# Motor-Y.net
KiCad netlist of a schematic drawn in Altium Designer
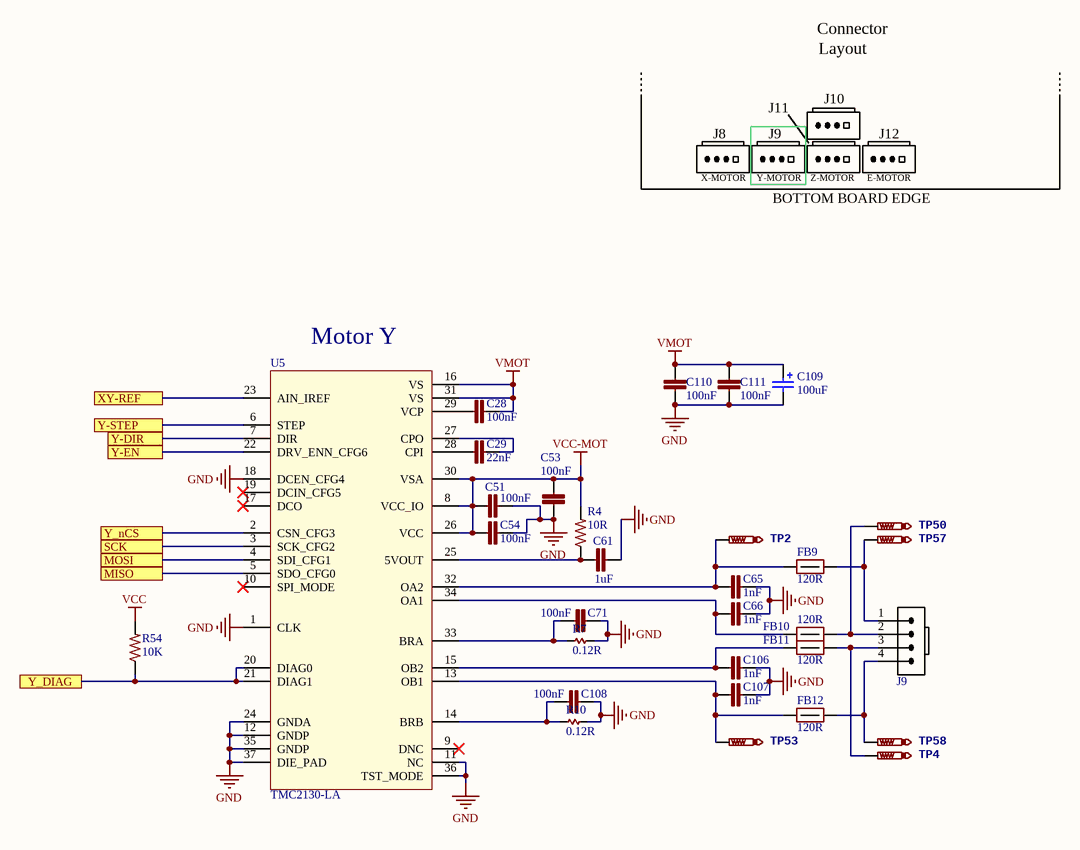
[diagram p0: Motor-Y.SchDoc]

(export (version "E")
  (design (tool "Eeschema 10.0.6"))
  (components
    (comp (ref "C28")
      (value "100nF")
      (footprint "C0603")
      (description "CAP CER 0603 100nF 50V 10% X7R")
      (fields (field (name "MANUFACTURER") "Kemet") (field (name "TOLERANCE") "+/- 10%"))
      (libsource (lib "") (part "C0603C104K5RACTU_1"))
    )
    (comp (ref "C29")
      (value "22nF")
      (footprint "C0402")
      (description "CAP CER 0402 22nF ±10% 50V X7R")
      (fields (field (name "MANUFACTURER") "YAGEO") (field (name "TOLERANCE") "+/- 10%"))
      (libsource (lib "3Delight") (part "GCM155R71H223KA55D"))
    )
    (comp (ref "C51")
      (value "100nF")
      (footprint "C0402")
      (description "CAP CER 0402 100nF 16V 10% X7R")
      (fields (field (name "MANUFACTURER") "Murata") (field (name "TOLERANCE") "+/- 10%"))
      (libsource (lib "3Delight") (part "GRM155R71C104KA88D"))
    )
    (comp (ref "C53")
      (value "100nF")
      (footprint "C0402")
      (description "CAP CER 0402 100nF 16V 10% X7R")
      (fields (field (name "MANUFACTURER") "Murata") (field (name "TOLERANCE") "+/- 10%"))
      (libsource (lib "") (part "GRM155R71C104KA88D_1"))
    )
    (comp (ref "C54")
      (value "100nF")
      (footprint "C0402")
      (description "CAP CER 0402 100nF 16V 10% X7R")
      (fields (field (name "MANUFACTURER") "Murata") (field (name "TOLERANCE") "+/- 10%"))
      (libsource (lib "3Delight") (part "GRM155R71C104KA88D"))
    )
    (comp (ref "C61")
      (value "1uF")
      (footprint "C0402")
      (description "CAP CER 0402 1uF 6.3V 10% X5R")
      (fields (field (name "MANUFACTURER") "Murata") (field (name "TOLERANCE") "+/- 10%"))
      (libsource (lib "3Delight") (part "GRM155R60J105KE19D"))
    )
    (comp (ref "C65")
      (value "1nF")
      (footprint "C0603")
      (description "CAP CER 0603  1nF 50v 10% X7R")
      (fields (field (name "MANUFACTURER") "Kemet") (field (name "TOLERANCE") "+/- 10%"))
      (libsource (lib "3Delight") (part "C0603C102K5RACTU"))
    )
    (comp (ref "C66")
      (value "1nF")
      (footprint "C0603")
      (description "CAP CER 0603  1nF 50v 10% X7R")
      (fields (field (name "MANUFACTURER") "Kemet") (field (name "TOLERANCE") "+/- 10%"))
      (libsource (lib "3Delight") (part "C0603C102K5RACTU"))
    )
    (comp (ref "C71")
      (value "100nF")
      (footprint "C0603")
      (description "CAP CER 0603 100nF 50V 10% X7R")
      (fields (field (name "MANUFACTURER") "Kemet") (field (name "TOLERANCE") "+/- 10%"))
      (libsource (lib "3Delight") (part "C0603C104K5RACTU"))
    )
    (comp (ref "C106")
      (value "1nF")
      (footprint "C0603")
      (description "CAP CER 0603  1nF 50v 10% X7R")
      (fields (field (name "MANUFACTURER") "Kemet") (field (name "TOLERANCE") "+/- 10%"))
      (libsource (lib "3Delight") (part "C0603C102K5RACTU"))
    )
    (comp (ref "C107")
      (value "1nF")
      (footprint "C0603")
      (description "CAP CER 0603  1nF 50v 10% X7R")
      (fields (field (name "MANUFACTURER") "Kemet") (field (name "TOLERANCE") "+/- 10%"))
      (libsource (lib "3Delight") (part "C0603C102K5RACTU"))
    )
    (comp (ref "C108")
      (value "100nF")
      (footprint "C0603")
      (description "CAP CER 0603 100nF 50V 10% X7R")
      (fields (field (name "MANUFACTURER") "Kemet") (field (name "TOLERANCE") "+/- 10%"))
      (libsource (lib "3Delight") (part "C0603C104K5RACTU"))
    )
    (comp (ref "C109")
      (value "100uF")
      (footprint "CAP-ELEC-063063077")
      (description "CAP ALUM 100UF 35V 20% SMD")
      (fields (field (name "MANUFACTURER") "Nichicon") (field (name "TOLERANCE") "+/- 20%"))
      (libsource (lib "3Delight") (part "UWT1V101MCL1GS"))
    )
    (comp (ref "C110")
      (value "100nF")
      (footprint "C0603")
      (description "CAP CER 0603 100nF 50V 10% X7R")
      (fields (field (name "MANUFACTURER") "Kemet") (field (name "TOLERANCE") "+/- 10%"))
      (libsource (lib "") (part "C0603C104K5RACTU_2"))
    )
    (comp (ref "C111")
      (value "100nF")
      (footprint "C0603")
      (description "CAP CER 0603 100nF 50V 10% X7R")
      (fields (field (name "MANUFACTURER") "Kemet") (field (name "TOLERANCE") "+/- 10%"))
      (libsource (lib "") (part "C0603C104K5RACTU_2"))
    )
    (comp (ref "FB9")
      (value "120R")
      (footprint "FB0603")
      (description "FERRITE BEAD 120 OHM 0603 1LN")
      (fields (field (name "MANUFACTURER") "Samsung") (field (name "PART") "FERRITE 120R 3A 0603"))
      (libsource (lib "Inductors") (part "FERRITE 120R 3A 0603"))
    )
    (comp (ref "FB10")
      (value "120R")
      (footprint "FB0603")
      (description "FERRITE BEAD 120 OHM 0603 1LN")
      (fields (field (name "MANUFACTURER") "Samsung") (field (name "PART") "FERRITE 120R 3A 0603"))
      (libsource (lib "Inductors") (part "FERRITE 120R 3A 0603"))
    )
    (comp (ref "FB11")
      (value "120R")
      (footprint "FB0603")
      (description "FERRITE BEAD 120 OHM 0603 1LN")
      (fields (field (name "MANUFACTURER") "Samsung") (field (name "PART") "FERRITE 120R 3A 0603"))
      (libsource (lib "Inductors") (part "FERRITE 120R 3A 0603"))
    )
    (comp (ref "FB12")
      (value "120R")
      (footprint "FB0603")
      (description "FERRITE BEAD 120 OHM 0603 1LN")
      (fields (field (name "MANUFACTURER") "Samsung") (field (name "PART") "FERRITE 120R 3A 0603"))
      (libsource (lib "Inductors") (part "FERRITE 120R 3A 0603"))
    )
    (comp (ref "J9")
      (value "Molex 0705430003")
      (footprint "4POL254 PIN-IN-PASTE")
      (description "Molex 4 Pin Clip Connector - Pin In Paste footprint")
      (libsource (lib "Connectors") (part "Molex 0705430003 PIP"))
    )
    (comp (ref "R4")
      (value "10R")
      (footprint "R0402")
      (description "RES SMD 10 OHM 1% 1/16W 0402")
      (fields (field (name "MANUFACTURER") "Yageo") (field (name "TOLERANCE") "+/- 1%"))
      (libsource (lib "3Delight") (part "RC0402FR-0710RL"))
    )
    (comp (ref "R7")
      (value "0.12R")
      (footprint "R1206")
      (description "RES 0.12 OHM 1% 1/2W 1206")
      (fields (field (name "TOLERANCE") "+/- 1%"))
      (libsource (lib "Resistors") (part "0.12R 1% 1206"))
    )
    (comp (ref "R10")
      (value "0.12R")
      (footprint "R1206")
      (description "RES 0.12 OHM 1% 1/2W 1206")
      (fields (field (name "TOLERANCE") "+/- 1%"))
      (libsource (lib "Resistors") (part "0.12R 1% 1206"))
    )
    (comp (ref "R54")
      (value "10K")
      (footprint "R0402")
      (description "RES SMD 10K OHM 1% 1/16W 0402")
      (fields (field (name "MANUFACTURER") "Yageo") (field (name "PART") "10k 1% 0402"))
      (libsource (lib "3Delight") (part "RC0402FR-0710KP"))
    )
    (comp (ref "TP2")
      (value "TestPoint")
      (footprint "TP1-27")
      (description "Test Point")
      (libsource (lib "3Delight") (part "TestPoint"))
    )
    (comp (ref "TP4")
      (value "TestPoint")
      (footprint "TP1-27")
      (description "Test Point")
      (libsource (lib "3Delight") (part "TestPoint"))
    )
    (comp (ref "TP50")
      (value "TestPoint")
      (footprint "TP1-27")
      (description "Test Point")
      (libsource (lib "3Delight") (part "TestPoint"))
    )
    (comp (ref "TP53")
      (value "TestPoint")
      (footprint "TP1-27")
      (description "Test Point")
      (libsource (lib "3Delight") (part "TestPoint"))
    )
    (comp (ref "TP57")
      (value "TestPoint")
      (footprint "TP1-27")
      (description "Test Point")
      (libsource (lib "3Delight") (part "TestPoint"))
    )
    (comp (ref "TP58")
      (value "TestPoint")
      (footprint "TP1-27")
      (description "Test Point")
      (libsource (lib "3Delight") (part "TestPoint"))
    )
    (comp (ref "U5")
      (value "TMC2130-LA")
      (footprint "QFN36-50P500X600X900_HS-37N")
      (description "IC STEPPER MOTOR DVR SPI 36QFN")
      (fields (field (name "MANUFACTURER") "Trinamic") (field (name "PART") "TMC2130"))
      (libsource (lib "3Delight") (part "TMC2130-LA-T"))
    )
  )
  (nets
    (net (code "1") (name "/MISO") (class "Default")
      (node (ref "U5") (pin "5") (pinfunction "SDO_CFG0_5") (pintype "passive"))
    )
    (net (code "2") (name "/MOSI") (class "Default")
      (node (ref "U5") (pin "4") (pinfunction "SDI_CFG1_4") (pintype "passive"))
    )
    (net (code "3") (name "/SCK") (class "Default")
      (node (ref "U5") (pin "3") (pinfunction "SCK_CFG2_3") (pintype "passive"))
    )
    (net (code "4") (name "/XY-REF") (class "Default")
      (node (ref "U5") (pin "23") (pinfunction "AIN_IREF_23") (pintype "passive"))
    )
    (net (code "5") (name "/Y-DIR") (class "Default")
      (node (ref "U5") (pin "7") (pinfunction "DIR_7") (pintype "passive"))
    )
    (net (code "6") (name "/Y-EN") (class "Default")
      (node (ref "U5") (pin "22") (pinfunction "DRV_ENN_CFG6_22") (pintype "passive"))
    )
    (net (code "7") (name "/Y-STEP") (class "Default")
      (node (ref "U5") (pin "6") (pinfunction "STEP_6") (pintype "passive"))
    )
    (net (code "8") (name "/Y_DIAG") (class "Default")
      (node (ref "R54") (pin "1") (pinfunction "1_1") (pintype "passive"))
      (node (ref "U5") (pin "20") (pinfunction "DIAG0_20") (pintype "passive"))
      (node (ref "U5") (pin "21") (pinfunction "DIAG1_21") (pintype "passive"))
    )
    (net (code "9") (name "/Y_nCS") (class "Default")
      (node (ref "U5") (pin "2") (pinfunction "CSN_CFG3_2") (pintype "passive"))
    )
    (net (code "10") (name "GND") (class "Default")
      (node (ref "C106") (pin "2") (pinfunction "2_2") (pintype "passive"))
      (node (ref "C107") (pin "2") (pinfunction "2_2") (pintype "passive"))
      (node (ref "C108") (pin "1") (pinfunction "1_1") (pintype "passive"))
      (node (ref "C109") (pin "2") (pinfunction "2_2") (pintype "passive"))
      (node (ref "C110") (pin "1") (pinfunction "1_1") (pintype "passive"))
      (node (ref "C111") (pin "1") (pinfunction "1_1") (pintype "passive"))
      (node (ref "C51") (pin "1") (pinfunction "1_1") (pintype "passive"))
      (node (ref "C53") (pin "1") (pinfunction "1_1") (pintype "passive"))
      (node (ref "C54") (pin "1") (pinfunction "1_1") (pintype "passive"))
      (node (ref "C61") (pin "2") (pinfunction "2_2") (pintype "passive"))
      (node (ref "C65") (pin "2") (pinfunction "2_2") (pintype "passive"))
      (node (ref "C66") (pin "2") (pinfunction "2_2") (pintype "passive"))
      (node (ref "C71") (pin "1") (pinfunction "1_1") (pintype "passive"))
      (node (ref "R10") (pin "2") (pinfunction "2_2") (pintype "passive"))
      (node (ref "R7") (pin "2") (pinfunction "2_2") (pintype "passive"))
      (node (ref "U5") (pin "1") (pinfunction "CLK_1") (pintype "passive"))
      (node (ref "U5") (pin "11") (pinfunction "NC_11") (pintype "passive"))
      (node (ref "U5") (pin "12") (pinfunction "GNDP_12") (pintype "passive"))
      (node (ref "U5") (pin "18") (pinfunction "DCEN_CFG4_18") (pintype "passive"))
      (node (ref "U5") (pin "24") (pinfunction "GNDA_24") (pintype "passive"))
      (node (ref "U5") (pin "35") (pinfunction "GNDP_35") (pintype "passive"))
      (node (ref "U5") (pin "36") (pinfunction "TST_MODE_36") (pintype "passive"))
      (node (ref "U5") (pin "37") (pinfunction "DIE_PAD_37") (pintype "passive"))
    )
    (net (code "11") (name "Net-(FB9-Pad2)") (class "Default")
      (node (ref "FB9") (pin "2") (pinfunction "2_2") (pintype "passive"))
      (node (ref "J9") (pin "1") (pinfunction "1_1") (pintype "passive"))
      (node (ref "TP57") (pin "TP") (pinfunction "TP_TP") (pintype "passive"))
    )
    (net (code "12") (name "Net-(FB10-Pad2)") (class "Default")
      (node (ref "FB10") (pin "2") (pinfunction "2_2") (pintype "passive"))
      (node (ref "J9") (pin "2") (pinfunction "2_2") (pintype "passive"))
      (node (ref "TP50") (pin "TP") (pinfunction "TP_TP") (pintype "passive"))
    )
    (net (code "13") (name "Net-(FB11-Pad2)") (class "Default")
      (node (ref "FB11") (pin "2") (pinfunction "2_2") (pintype "passive"))
      (node (ref "J9") (pin "3") (pinfunction "3_3") (pintype "passive"))
      (node (ref "TP4") (pin "TP") (pinfunction "TP_TP") (pintype "passive"))
    )
    (net (code "14") (name "Net-(FB12-Pad2)") (class "Default")
      (node (ref "FB12") (pin "2") (pinfunction "2_2") (pintype "passive"))
      (node (ref "J9") (pin "4") (pinfunction "4_4") (pintype "passive"))
      (node (ref "TP58") (pin "TP") (pinfunction "TP_TP") (pintype "passive"))
    )
    (net (code "15") (name "Net-(U5-5VOUT)") (class "Default")
      (node (ref "C61") (pin "1") (pinfunction "1_1") (pintype "passive"))
      (node (ref "R4") (pin "1") (pinfunction "1_1") (pintype "passive"))
      (node (ref "U5") (pin "25") (pinfunction "5VOUT_25") (pintype "passive"))
    )
    (net (code "16") (name "Net-(U5-BRA)") (class "Default")
      (node (ref "C71") (pin "2") (pinfunction "2_2") (pintype "passive"))
      (node (ref "R7") (pin "1") (pinfunction "1_1") (pintype "passive"))
      (node (ref "U5") (pin "33") (pinfunction "BRA_33") (pintype "passive"))
    )
    (net (code "17") (name "Net-(U5-BRB)") (class "Default")
      (node (ref "C108") (pin "2") (pinfunction "2_2") (pintype "passive"))
      (node (ref "R10") (pin "1") (pinfunction "1_1") (pintype "passive"))
      (node (ref "U5") (pin "14") (pinfunction "BRB_14") (pintype "passive"))
    )
    (net (code "18") (name "Net-(U5-CPI)") (class "Default")
      (node (ref "C29") (pin "1") (pinfunction "1_1") (pintype "passive"))
      (node (ref "U5") (pin "28") (pinfunction "CPI_28") (pintype "passive"))
    )
    (net (code "19") (name "Net-(U5-CPO)") (class "Default")
      (node (ref "C29") (pin "2") (pinfunction "2_2") (pintype "passive"))
      (node (ref "U5") (pin "27") (pinfunction "CPO_27") (pintype "passive"))
    )
    (net (code "20") (name "Net-(U5-OA1)") (class "Default")
      (node (ref "C66") (pin "1") (pinfunction "1_1") (pintype "passive"))
      (node (ref "FB10") (pin "1") (pinfunction "1_1") (pintype "passive"))
      (node (ref "U5") (pin "34") (pinfunction "OA1_34") (pintype "passive"))
    )
    (net (code "21") (name "Net-(U5-OA2)") (class "Default")
      (node (ref "C65") (pin "1") (pinfunction "1_1") (pintype "passive"))
      (node (ref "FB9") (pin "1") (pinfunction "1_1") (pintype "passive"))
      (node (ref "TP2") (pin "TP") (pinfunction "TP_TP") (pintype "passive"))
      (node (ref "U5") (pin "32") (pinfunction "OA2_32") (pintype "passive"))
    )
    (net (code "22") (name "Net-(U5-OB1)") (class "Default")
      (node (ref "C107") (pin "1") (pinfunction "1_1") (pintype "passive"))
      (node (ref "FB12") (pin "1") (pinfunction "1_1") (pintype "passive"))
      (node (ref "TP53") (pin "TP") (pinfunction "TP_TP") (pintype "passive"))
      (node (ref "U5") (pin "13") (pinfunction "OB1_13") (pintype "passive"))
    )
    (net (code "23") (name "Net-(U5-OB2)") (class "Default")
      (node (ref "C106") (pin "1") (pinfunction "1_1") (pintype "passive"))
      (node (ref "FB11") (pin "1") (pinfunction "1_1") (pintype "passive"))
      (node (ref "U5") (pin "15") (pinfunction "OB2_15") (pintype "passive"))
    )
    (net (code "24") (name "Net-(U5-VCP)") (class "Default")
      (node (ref "C28") (pin "1") (pinfunction "1_1") (pintype "passive"))
      (node (ref "U5") (pin "29") (pinfunction "VCP_29") (pintype "passive"))
    )
    (net (code "25") (name "VCC") (class "Default")
      (node (ref "R54") (pin "2") (pinfunction "2_2") (pintype "passive"))
    )
    (net (code "26") (name "VCC-MOT") (class "Default")
      (node (ref "C51") (pin "2") (pinfunction "2_2") (pintype "passive"))
      (node (ref "C53") (pin "2") (pinfunction "2_2") (pintype "passive"))
      (node (ref "C54") (pin "2") (pinfunction "2_2") (pintype "passive"))
      (node (ref "R4") (pin "2") (pinfunction "2_2") (pintype "passive"))
      (node (ref "U5") (pin "26") (pinfunction "VCC_26") (pintype "passive"))
      (node (ref "U5") (pin "30") (pinfunction "VSA_30") (pintype "passive"))
      (node (ref "U5") (pin "8") (pinfunction "VCC_IO_8") (pintype "passive"))
    )
    (net (code "27") (name "VMOT") (class "Default")
      (node (ref "C109") (pin "1") (pinfunction "1_1") (pintype "passive"))
      (node (ref "C110") (pin "2") (pinfunction "2_2") (pintype "passive"))
      (node (ref "C111") (pin "2") (pinfunction "2_2") (pintype "passive"))
      (node (ref "C28") (pin "2") (pinfunction "2_2") (pintype "passive"))
      (node (ref "U5") (pin "16") (pinfunction "VS_16") (pintype "passive"))
      (node (ref "U5") (pin "31") (pinfunction "VS_31") (pintype "passive"))
    )
    (net (code "28") (name "unconnected-(U5-DCIN_CFG5-Pad19)") (class "Default")
      (node (ref "U5") (pin "19") (pinfunction "DCIN_CFG5_19") (pintype "passive+no_connect"))
    )
    (net (code "29") (name "unconnected-(U5-DCO-Pad17)") (class "Default")
      (node (ref "U5") (pin "17") (pinfunction "DCO_17") (pintype "passive+no_connect"))
    )
    (net (code "30") (name "unconnected-(U5-DNC-Pad9)") (class "Default")
      (node (ref "U5") (pin "9") (pinfunction "DNC_9") (pintype "passive+no_connect"))
    )
    (net (code "31") (name "unconnected-(U5-SPI_MODE-Pad10)") (class "Default")
      (node (ref "U5") (pin "10") (pinfunction "SPI_MODE_10") (pintype "passive+no_connect"))
    )
  )
)
